# Golf_Cart_Schematic.net
KiCad netlist of a schematic drawn in EAGLE
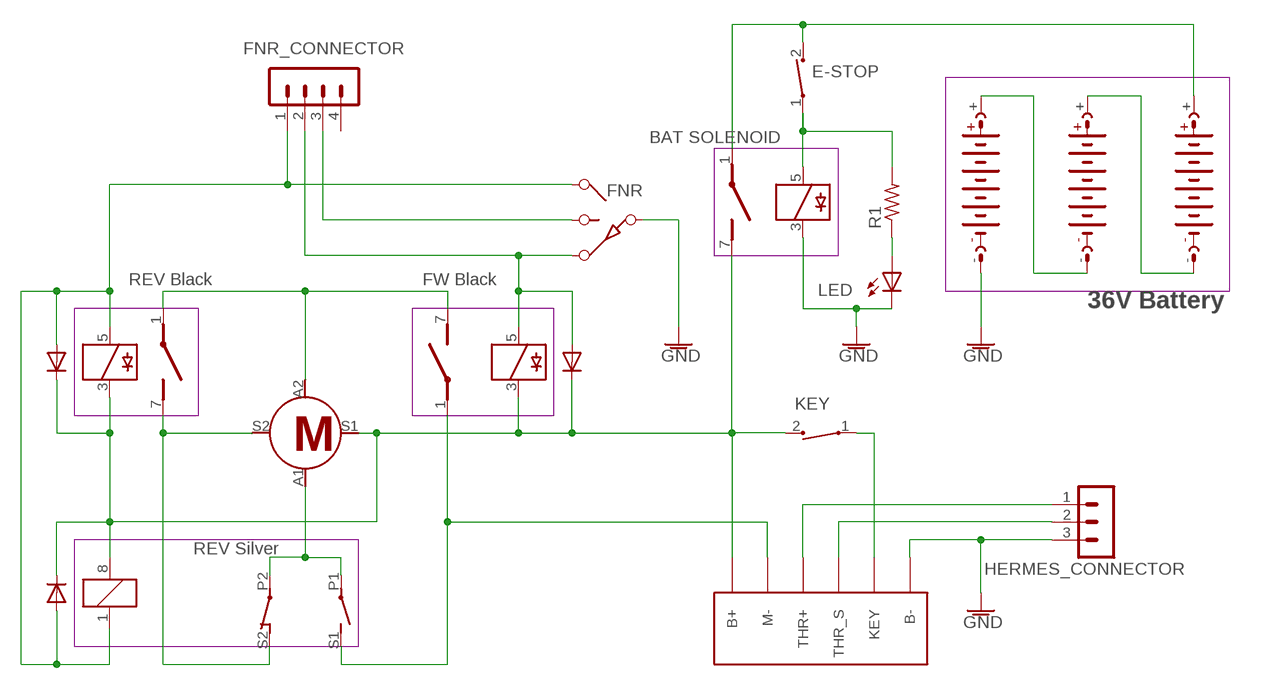
[diagram p0: schematic, sheet 1]

(export (version "E")
  (design (tool "Eeschema 10.0.6"))
  (components
    (comp (ref "D1")
      (value "1N4933")
      (footprint "eagle-import:DO41-10")
      (libsource (lib "eagle-import") (part "1N4933"))
    )
    (comp (ref "D2")
      (value "1N4933")
      (footprint "eagle-import:DO41-10")
      (libsource (lib "eagle-import") (part "1N4933"))
    )
    (comp (ref "D3")
      (value "1N4933")
      (footprint "eagle-import:DO41-10")
      (libsource (lib "eagle-import") (part "1N4933"))
    )
    (comp (ref "E-STOP")
      (value "CT10-XXXX-G1")
      (footprint "eagle-import:CT10-XXXX-G1")
      (libsource (lib "eagle-import") (part "CT10-XXXX-G1"))
    )
    (comp (ref "FNR_CONNECTOR")
      (value "MA04-1")
      (footprint "eagle-import:MA04-1")
      (libsource (lib "eagle-import") (part "MA04-1"))
    )
    (comp (ref "G1")
      (value "AB9V")
      (footprint "eagle-import:AB9V")
      (libsource (lib "eagle-import") (part "AB9V"))
    )
    (comp (ref "G2")
      (value "AB9V")
      (footprint "eagle-import:AB9V")
      (libsource (lib "eagle-import") (part "AB9V"))
    )
    (comp (ref "G3")
      (value "AB9V")
      (footprint "eagle-import:AB9V")
      (libsource (lib "eagle-import") (part "AB9V"))
    )
    (comp (ref "HERMES_CONNECTOR")
      (value "MA03-1")
      (footprint "eagle-import:MA03-1")
      (libsource (lib "eagle-import") (part "MA03-1"))
    )
    (comp (ref "K1")
      (value "BAT SOLENOID")
      (footprint "eagle-import:REED")
      (libsource (lib "eagle-import") (part "35701331"))
    )
    (comp (ref "K2")
      (value "REV Silver")
      (footprint "eagle-import:G6C-2117P")
      (libsource (lib "eagle-import") (part "G6C-2117P"))
    )
    (comp (ref "K4")
      (value "REV Black")
      (footprint "eagle-import:REED")
      (libsource (lib "eagle-import") (part "35701331"))
    )
    (comp (ref "K5")
      (value "FW Black")
      (footprint "eagle-import:REED")
      (libsource (lib "eagle-import") (part "35701331"))
    )
    (comp (ref "KEY")
      (value "CT10-XXXX-G1")
      (footprint "eagle-import:CT10-XXXX-G1")
      (libsource (lib "eagle-import") (part "CT10-XXXX-G1"))
    )
    (comp (ref "LED")
      (value "LED_E")
      (footprint "eagle-import:LED_1206")
      (libsource (lib "eagle-import") (part "LED_E"))
    )
    (comp (ref "R1")
      (value "R-US_0204/7")
      (footprint "eagle-import:0204_7")
      (libsource (lib "eagle-import") (part "R-US_0204/7"))
    )
    (comp (ref "U$1")
      (value "MOTOR_PH")
      (footprint "eagle-import:MOTOR_PH")
      (libsource (lib "eagle-import") (part "MOTOR_PH"))
    )
    (comp (ref "U$2")
      (value "THROTTLE_CTRL")
      (footprint "eagle-import:THROTTLE_CTRL")
      (libsource (lib "eagle-import") (part "THROTTLE_CTRL"))
    )
    (comp (ref "U$3")
      (value "FNR")
      (footprint "eagle-import:FNR")
      (libsource (lib "eagle-import") (part "FNR"))
    )
  )
  (nets
    (net (code "1") (name "GND") (class "Default")
      (node (ref "G2") (pin "-") (pinfunction "-_-") (pintype "passive"))
      (node (ref "HERMES_CONNECTOR") (pin "3") (pinfunction "3_3") (pintype "passive"))
      (node (ref "K1") (pin "3") (pinfunction "3_3") (pintype "passive"))
      (node (ref "LED") (pin "C") (pinfunction "C_C") (pintype "passive"))
      (node (ref "U$2") (pin "P$2") (pinfunction "B-_P$2") (pintype "bidirectional"))
      (node (ref "U$3") (pin "P$4") (pinfunction "C_P$4") (pintype "passive"))
    )
    (net (code "2") (name "Net-(E-STOP-Pad1)") (class "Default")
      (node (ref "E-STOP") (pin "1") (pinfunction "1_1") (pintype "passive"))
      (node (ref "K1") (pin "5") (pinfunction "5_5") (pintype "passive"))
      (node (ref "R1") (pin "2") (pinfunction "2_2") (pintype "passive"))
    )
    (net (code "3") (name "Net-(G1-Pad+)") (class "Default")
      (node (ref "G1") (pin "+") (pinfunction "+_+") (pintype "passive"))
      (node (ref "G3") (pin "-") (pinfunction "-_-") (pintype "passive"))
    )
    (net (code "4") (name "Net-(G1-Pad-)") (class "Default")
      (node (ref "G1") (pin "-") (pinfunction "-_-") (pintype "passive"))
      (node (ref "G2") (pin "+") (pinfunction "+_+") (pintype "passive"))
    )
    (net (code "5") (name "Net-(K1B-P)") (class "Default")
      (node (ref "E-STOP") (pin "2") (pinfunction "2_2") (pintype "passive"))
      (node (ref "G3") (pin "+") (pinfunction "+_+") (pintype "passive"))
      (node (ref "K1") (pin "1") (pinfunction "P_1") (pintype "passive"))
    )
    (net (code "6") (name "Net-(K1B-S)") (class "Default")
      (node (ref "D1") (pin "C") (pinfunction "C_C") (pintype "passive"))
      (node (ref "D2") (pin "C") (pinfunction "C_C") (pintype "passive"))
      (node (ref "D3") (pin "C") (pinfunction "C_C") (pintype "passive"))
      (node (ref "K1") (pin "7") (pinfunction "S_7") (pintype "passive"))
      (node (ref "K2") (pin "8") (pinfunction "2_8") (pintype "passive"))
      (node (ref "K4") (pin "3") (pinfunction "3_3") (pintype "passive"))
      (node (ref "K5") (pin "3") (pinfunction "3_3") (pintype "passive"))
      (node (ref "KEY") (pin "2") (pinfunction "2_2") (pintype "passive"))
      (node (ref "U$1") (pin "S1") (pinfunction "S1_S1") (pintype "power_in"))
      (node (ref "U$2") (pin "P$1") (pinfunction "B+_P$1") (pintype "bidirectional"))
    )
    (net (code "7") (name "Net-(K2B-P)") (class "Default")
      (node (ref "K2") (pin "P1") (pinfunction "P_P1") (pintype "passive"))
      (node (ref "K2") (pin "P2") (pinfunction "P_P2") (pintype "passive"))
      (node (ref "U$1") (pin "A1") (pinfunction "A1_A1") (pintype "power_in"))
    )
    (net (code "8") (name "Net-(K2B-S)") (class "Default")
      (node (ref "K2") (pin "S1") (pinfunction "S_S1") (pintype "passive"))
      (node (ref "K5") (pin "1") (pinfunction "P_1") (pintype "passive"))
      (node (ref "U$2") (pin "P$4") (pinfunction "M-_P$4") (pintype "bidirectional"))
    )
    (net (code "9") (name "Net-(K2C-O)") (class "Default")
      (node (ref "K2") (pin "S2") (pinfunction "O_S2") (pintype "passive"))
      (node (ref "K4") (pin "7") (pinfunction "S_7") (pintype "passive"))
      (node (ref "U$1") (pin "S2") (pinfunction "S2_S2") (pintype "power_in"))
    )
    (net (code "10") (name "Net-(K4B-P)") (class "Default")
      (node (ref "K4") (pin "1") (pinfunction "P_1") (pintype "passive"))
      (node (ref "K5") (pin "7") (pinfunction "S_7") (pintype "passive"))
      (node (ref "U$1") (pin "A2") (pinfunction "A2_A2") (pintype "power_in"))
    )
    (net (code "11") (name "Net-(LED-PadA)") (class "Default")
      (node (ref "LED") (pin "A") (pinfunction "A_A") (pintype "passive"))
      (node (ref "R1") (pin "1") (pinfunction "1_1") (pintype "passive"))
    )
    (net (code "12") (name "Net-(U$2-KEY)") (class "Default")
      (node (ref "KEY") (pin "1") (pinfunction "1_1") (pintype "passive"))
      (node (ref "U$2") (pin "P$3") (pinfunction "KEY_P$3") (pintype "bidirectional"))
    )
    (net (code "13") (name "Net-(U$2-THR+)") (class "Default")
      (node (ref "HERMES_CONNECTOR") (pin "1") (pinfunction "1_1") (pintype "passive"))
      (node (ref "U$2") (pin "P$5") (pinfunction "THR+_P$5") (pintype "bidirectional"))
    )
    (net (code "14") (name "Net-(U$2-THR_S)") (class "Default")
      (node (ref "HERMES_CONNECTOR") (pin "2") (pinfunction "2_2") (pintype "passive"))
      (node (ref "U$2") (pin "P$6") (pinfunction "THR_S_P$6") (pintype "bidirectional"))
    )
    (net (code "15") (name "Net-(U$3-1)") (class "Default")
      (node (ref "D1") (pin "A") (pinfunction "A_A") (pintype "passive"))
      (node (ref "D2") (pin "A") (pinfunction "A_A") (pintype "passive"))
      (node (ref "FNR_CONNECTOR") (pin "1") (pinfunction "1_1") (pintype "passive"))
      (node (ref "K2") (pin "1") (pinfunction "1_1") (pintype "passive"))
      (node (ref "K4") (pin "5") (pinfunction "5_5") (pintype "passive"))
      (node (ref "U$3") (pin "P$1") (pinfunction "1_P$1") (pintype "passive"))
    )
    (net (code "16") (name "Net-(U$3-2)") (class "Default")
      (node (ref "FNR_CONNECTOR") (pin "3") (pinfunction "3_3") (pintype "passive"))
      (node (ref "U$3") (pin "P$2") (pinfunction "2_P$2") (pintype "passive"))
    )
    (net (code "17") (name "Net-(U$3-4)") (class "Default")
      (node (ref "D3") (pin "A") (pinfunction "A_A") (pintype "passive"))
      (node (ref "FNR_CONNECTOR") (pin "2") (pinfunction "2_2") (pintype "passive"))
      (node (ref "K5") (pin "5") (pinfunction "5_5") (pintype "passive"))
      (node (ref "U$3") (pin "P$3") (pinfunction "4_P$3") (pintype "passive"))
    )
    (net (code "18") (name "unconnected-(FNR_CONNECTOR-Pad4)") (class "Default")
      (node (ref "FNR_CONNECTOR") (pin "4") (pinfunction "4_4") (pintype "passive"))
    )
  )
)
